# ESP32.net
KiCad netlist of a schematic drawn in Altium Designer
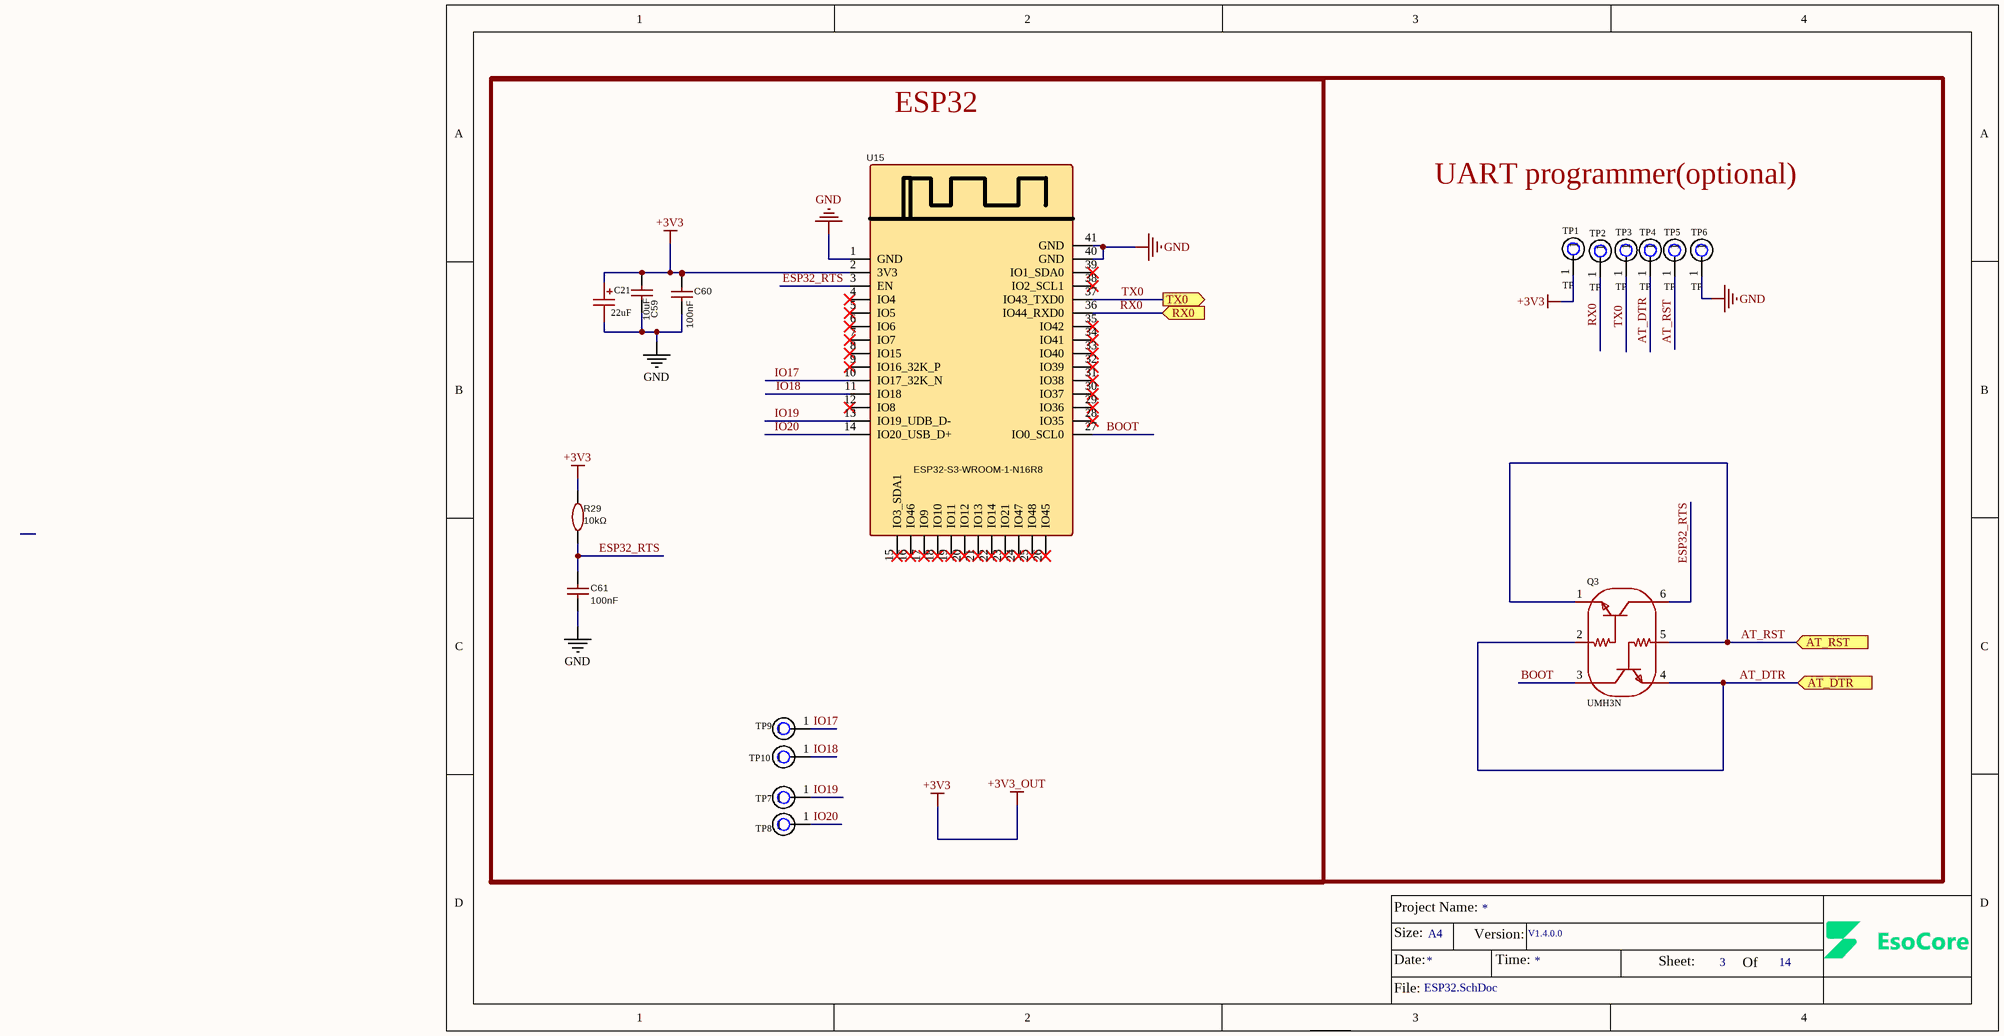
[diagram p0: ESP32.SchDoc]

(export (version "E")
  (design (tool "Eeschema 10.0.6"))
  (components
    (comp (ref "C21")
      (value "22uF")
      (footprint "CASE-A_3216")
      (fields
        (field (name "MANUFACTURER") "Kyocera AVX")
        (field (name "MANUFACTURER PART") "TAJA226K010RNJ")
        (field (name "TOLERANCE") "±10%")
      )
      (libsource (lib "altium-import") (part "root_1_TAJA226K010RNJ_"))
    )
    (comp (ref "C59")
      (value "10uF")
      (footprint "C_0805")
      (fields
        (field (name "MANUFACTURER PART") "CL21A106KOQNNNE")
        (field (name "MANUFACTURER") "SAMSUNG(三星)")
      )
      (libsource (lib "altium-import") (part "root_1_mirrored_10uF_"))
    )
    (comp (ref "C60")
      (value "100nF")
      (footprint "C_0805")
      (fields
        (field (name "MANUFACTURER PART") "CL21B104KBCNNNC")
        (field (name "MANUFACTURER") "SAMSUNG(三星)")
      )
      (libsource (lib "altium-import") (part "root_1_100nF_"))
    )
    (comp (ref "C61")
      (value "100nF")
      (footprint "C_0805")
      (fields
        (field (name "MANUFACTURER PART") "CL21B104KBCNNNC")
        (field (name "MANUFACTURER") "SAMSUNG(三星)")
      )
      (libsource (lib "altium-import") (part "root_1_100nF_"))
    )
    (comp (ref "Q3")
      (value "UMH3N")
      (footprint "SC-70-6_L2.2-W1.3-P0.65-LS2.1-BR")
      (fields (field (name "MANUFACTURER") "CJ(江苏长电/长晶)"))
      (libsource (lib "altium-import") (part "root_3_UMH3N_"))
    )
    (comp (ref "R29")
      (value "10kΩ")
      (footprint "R_0805")
      (fields (field (name "MANUFACTURER") "YAGEO(国巨)") (field (name "MANUFACTURER PART") "RC0805FR-0710KL"))
      (libsource (lib "altium-import") (part "root_1_10kΩ_"))
    )
    (comp (ref "TP1") (value "TP") (footprint "TP") (libsource (lib "Schlib1") (part "TP")))
    (comp (ref "TP2") (value "TP") (footprint "TP") (libsource (lib "Schlib1") (part "TP")))
    (comp (ref "TP3") (value "TP") (footprint "TP") (libsource (lib "Schlib1") (part "TP")))
    (comp (ref "TP4") (value "TP") (footprint "TP") (libsource (lib "Schlib1") (part "TP")))
    (comp (ref "TP5") (value "TP") (footprint "TP") (libsource (lib "Schlib1") (part "TP")))
    (comp (ref "TP6") (value "TP") (footprint "TP") (libsource (lib "Schlib1") (part "TP")))
    (comp (ref "TP7") (value "TP") (footprint "TP") (libsource (lib "Schlib1") (part "TP")))
    (comp (ref "TP8") (value "TP") (footprint "TP") (libsource (lib "Schlib1") (part "TP")))
    (comp (ref "TP9") (value "TP") (footprint "TP") (libsource (lib "Schlib1") (part "TP")))
    (comp (ref "TP10") (value "TP") (footprint "TP") (libsource (lib "Schlib1") (part "TP")))
    (comp (ref "U15")
      (value "ESP32-S3-WROOM-1-N16R8")
      (footprint "WIRELM-SMD_ESP32-S3-WROOM-1")
      (fields (field (name "MANUFACTURER") "ESPRESSIF(乐鑫)") (field (name "CONTRIBUTOR") "lcsc"))
      (libsource (lib "Schlib1") (part "ESP32-S3-WROOM-1-N16R8"))
    )
  )
  (nets
    (net (code "1") (name "+3V3") (class "Default")
      (node (ref "C21") (pin "1") (pinfunction "1_1") (pintype "passive"))
      (node (ref "C59") (pin "2") (pinfunction "2_2") (pintype "passive"))
      (node (ref "C60") (pin "2") (pinfunction "2_2") (pintype "passive"))
      (node (ref "R29") (pin "2") (pinfunction "2_2") (pintype "passive"))
      (node (ref "TP1") (pin "1") (pinfunction "1_1") (pintype "passive"))
      (node (ref "U15") (pin "2") (pinfunction "3V3_2") (pintype "passive"))
    )
    (net (code "2") (name "/AT_DTR") (class "Default")
      (node (ref "Q3") (pin "2") (pinfunction "B_2") (pintype "passive"))
      (node (ref "Q3") (pin "4") (pinfunction "E_4") (pintype "passive"))
      (node (ref "TP4") (pin "1") (pinfunction "1_1") (pintype "passive"))
    )
    (net (code "3") (name "/AT_RST") (class "Default")
      (node (ref "Q3") (pin "1") (pinfunction "E_1") (pintype "passive"))
      (node (ref "Q3") (pin "5") (pinfunction "B_5") (pintype "passive"))
      (node (ref "TP5") (pin "1") (pinfunction "1_1") (pintype "passive"))
    )
    (net (code "4") (name "/BOOT") (class "Default")
      (node (ref "Q3") (pin "3") (pinfunction "C_3") (pintype "passive"))
      (node (ref "U15") (pin "27") (pinfunction "IO0_SCL0_27") (pintype "passive"))
    )
    (net (code "5") (name "/ESP32_RTS") (class "Default")
      (node (ref "C61") (pin "2") (pinfunction "2_2") (pintype "passive"))
      (node (ref "Q3") (pin "6") (pinfunction "C_6") (pintype "passive"))
      (node (ref "R29") (pin "1") (pinfunction "1_1") (pintype "passive"))
      (node (ref "U15") (pin "3") (pinfunction "EN_3") (pintype "passive"))
    )
    (net (code "6") (name "/IO17") (class "Default")
      (node (ref "TP9") (pin "1") (pinfunction "1_1") (pintype "passive"))
      (node (ref "U15") (pin "10") (pinfunction "IO17_32K_N_10") (pintype "passive"))
    )
    (net (code "7") (name "/IO18") (class "Default")
      (node (ref "TP10") (pin "1") (pinfunction "1_1") (pintype "passive"))
      (node (ref "U15") (pin "11") (pinfunction "IO18_11") (pintype "passive"))
    )
    (net (code "8") (name "/IO19") (class "Default")
      (node (ref "TP7") (pin "1") (pinfunction "1_1") (pintype "passive"))
      (node (ref "U15") (pin "13") (pinfunction "IO19_UDB_D-_13") (pintype "passive"))
    )
    (net (code "9") (name "/IO20") (class "Default")
      (node (ref "TP8") (pin "1") (pinfunction "1_1") (pintype "passive"))
      (node (ref "U15") (pin "14") (pinfunction "IO20_USB_D+_14") (pintype "passive"))
    )
    (net (code "10") (name "/RX0") (class "Default")
      (node (ref "TP2") (pin "1") (pinfunction "1_1") (pintype "passive"))
      (node (ref "U15") (pin "36") (pinfunction "IO44_RXD0_36") (pintype "passive"))
    )
    (net (code "11") (name "/TX0") (class "Default")
      (node (ref "TP3") (pin "1") (pinfunction "1_1") (pintype "passive"))
      (node (ref "U15") (pin "37") (pinfunction "IO43_TXD0_37") (pintype "passive"))
    )
    (net (code "12") (name "GND") (class "Default")
      (node (ref "C21") (pin "2") (pinfunction "2_2") (pintype "passive"))
      (node (ref "C59") (pin "1") (pinfunction "1_1") (pintype "passive"))
      (node (ref "C60") (pin "1") (pinfunction "1_1") (pintype "passive"))
      (node (ref "C61") (pin "1") (pinfunction "1_1") (pintype "passive"))
      (node (ref "TP6") (pin "1") (pinfunction "1_1") (pintype "passive"))
      (node (ref "U15") (pin "1") (pinfunction "GND_1") (pintype "passive"))
      (node (ref "U15") (pin "40") (pinfunction "GND_40") (pintype "passive"))
      (node (ref "U15") (pin "41") (pinfunction "GND_41") (pintype "passive"))
    )
    (net (code "13") (name "unconnected-(U15-IO1_SDA0-Pad39)") (class "Default")
      (node (ref "U15") (pin "39") (pinfunction "IO1_SDA0_39") (pintype "passive+no_connect"))
    )
    (net (code "14") (name "unconnected-(U15-IO2_SCL1-Pad38)") (class "Default")
      (node (ref "U15") (pin "38") (pinfunction "IO2_SCL1_38") (pintype "passive+no_connect"))
    )
    (net (code "15") (name "unconnected-(U15-IO3_SDA1-Pad15)") (class "Default")
      (node (ref "U15") (pin "15") (pinfunction "IO3_SDA1_15") (pintype "passive+no_connect"))
    )
    (net (code "16") (name "unconnected-(U15-IO4-Pad4)") (class "Default")
      (node (ref "U15") (pin "4") (pinfunction "IO4_4") (pintype "passive+no_connect"))
    )
    (net (code "17") (name "unconnected-(U15-IO5-Pad5)") (class "Default")
      (node (ref "U15") (pin "5") (pinfunction "IO5_5") (pintype "passive+no_connect"))
    )
    (net (code "18") (name "unconnected-(U15-IO6-Pad6)") (class "Default")
      (node (ref "U15") (pin "6") (pinfunction "IO6_6") (pintype "passive+no_connect"))
    )
    (net (code "19") (name "unconnected-(U15-IO7-Pad7)") (class "Default")
      (node (ref "U15") (pin "7") (pinfunction "IO7_7") (pintype "passive+no_connect"))
    )
    (net (code "20") (name "unconnected-(U15-IO8-Pad12)") (class "Default")
      (node (ref "U15") (pin "12") (pinfunction "IO8_12") (pintype "passive+no_connect"))
    )
    (net (code "21") (name "unconnected-(U15-IO9-Pad17)") (class "Default")
      (node (ref "U15") (pin "17") (pinfunction "IO9_17") (pintype "passive+no_connect"))
    )
    (net (code "22") (name "unconnected-(U15-IO10-Pad18)") (class "Default")
      (node (ref "U15") (pin "18") (pinfunction "IO10_18") (pintype "passive+no_connect"))
    )
    (net (code "23") (name "unconnected-(U15-IO11-Pad19)") (class "Default")
      (node (ref "U15") (pin "19") (pinfunction "IO11_19") (pintype "passive+no_connect"))
    )
    (net (code "24") (name "unconnected-(U15-IO12-Pad20)") (class "Default")
      (node (ref "U15") (pin "20") (pinfunction "IO12_20") (pintype "passive+no_connect"))
    )
    (net (code "25") (name "unconnected-(U15-IO13-Pad21)") (class "Default")
      (node (ref "U15") (pin "21") (pinfunction "IO13_21") (pintype "passive+no_connect"))
    )
    (net (code "26") (name "unconnected-(U15-IO14-Pad22)") (class "Default")
      (node (ref "U15") (pin "22") (pinfunction "IO14_22") (pintype "passive+no_connect"))
    )
    (net (code "27") (name "unconnected-(U15-IO15-Pad8)") (class "Default")
      (node (ref "U15") (pin "8") (pinfunction "IO15_8") (pintype "passive+no_connect"))
    )
    (net (code "28") (name "unconnected-(U15-IO16_32K_P-Pad9)") (class "Default")
      (node (ref "U15") (pin "9") (pinfunction "IO16_32K_P_9") (pintype "passive+no_connect"))
    )
    (net (code "29") (name "unconnected-(U15-IO21-Pad23)") (class "Default")
      (node (ref "U15") (pin "23") (pinfunction "IO21_23") (pintype "passive+no_connect"))
    )
    (net (code "30") (name "unconnected-(U15-IO35-Pad28)") (class "Default")
      (node (ref "U15") (pin "28") (pinfunction "IO35_28") (pintype "passive+no_connect"))
    )
    (net (code "31") (name "unconnected-(U15-IO36-Pad29)") (class "Default")
      (node (ref "U15") (pin "29") (pinfunction "IO36_29") (pintype "passive+no_connect"))
    )
    (net (code "32") (name "unconnected-(U15-IO37-Pad30)") (class "Default")
      (node (ref "U15") (pin "30") (pinfunction "IO37_30") (pintype "passive+no_connect"))
    )
    (net (code "33") (name "unconnected-(U15-IO38-Pad31)") (class "Default")
      (node (ref "U15") (pin "31") (pinfunction "IO38_31") (pintype "passive+no_connect"))
    )
    (net (code "34") (name "unconnected-(U15-IO39-Pad32)") (class "Default")
      (node (ref "U15") (pin "32") (pinfunction "IO39_32") (pintype "passive+no_connect"))
    )
    (net (code "35") (name "unconnected-(U15-IO40-Pad33)") (class "Default")
      (node (ref "U15") (pin "33") (pinfunction "IO40_33") (pintype "passive+no_connect"))
    )
    (net (code "36") (name "unconnected-(U15-IO41-Pad34)") (class "Default")
      (node (ref "U15") (pin "34") (pinfunction "IO41_34") (pintype "passive+no_connect"))
    )
    (net (code "37") (name "unconnected-(U15-IO42-Pad35)") (class "Default")
      (node (ref "U15") (pin "35") (pinfunction "IO42_35") (pintype "passive+no_connect"))
    )
    (net (code "38") (name "unconnected-(U15-IO45-Pad26)") (class "Default")
      (node (ref "U15") (pin "26") (pinfunction "IO45_26") (pintype "passive+no_connect"))
    )
    (net (code "39") (name "unconnected-(U15-IO46-Pad16)") (class "Default")
      (node (ref "U15") (pin "16") (pinfunction "IO46_16") (pintype "passive+no_connect"))
    )
    (net (code "40") (name "unconnected-(U15-IO47-Pad24)") (class "Default")
      (node (ref "U15") (pin "24") (pinfunction "IO47_24") (pintype "passive+no_connect"))
    )
    (net (code "41") (name "unconnected-(U15-IO48-Pad25)") (class "Default")
      (node (ref "U15") (pin "25") (pinfunction "IO48_25") (pintype "passive+no_connect"))
    )
  )
)
